# IR_Receiver.net
KiCad netlist of a schematic drawn in Altium Designer
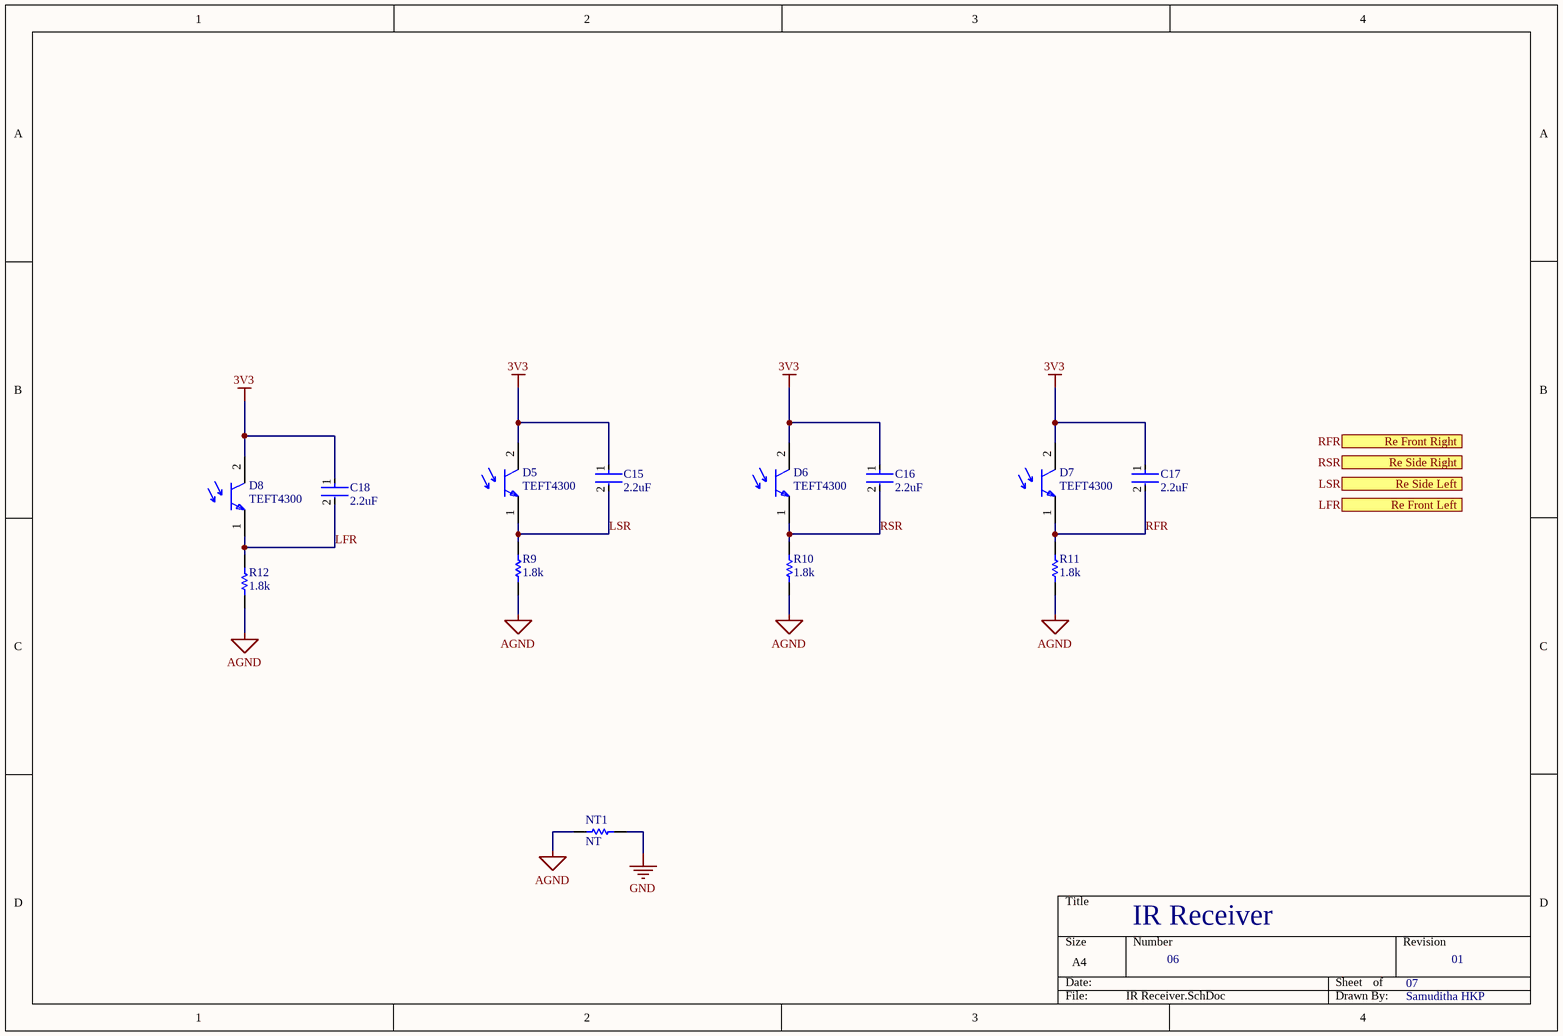
[diagram p0: IR Receiver.SchDoc]

(export (version "E")
  (design (tool "Eeschema 10.0.6"))
  (components
    (comp (ref "C15")
      (value "2.2uF")
      (footprint "FP-C0402C225M9PACTU-MFG")
      (description "CAP CER 2.2UF 6.3V X5R 0402")
      (fields (field (name "VOLTAGE") "6.3V") (field (name "TOLERANCE") "20%"))
      (libsource (lib "Altium Content Vault") (part "b4654b650e69147ec39a6b967a45e02"))
    )
    (comp (ref "C16")
      (value "2.2uF")
      (footprint "FP-C0402C225M9PACTU-MFG")
      (description "CAP CER 2.2UF 6.3V X5R 0402")
      (fields (field (name "VOLTAGE") "6.3V") (field (name "TOLERANCE") "20%"))
      (libsource (lib "Altium Content Vault") (part "b4654b650e69147ec39a6b967a45e02"))
    )
    (comp (ref "C17")
      (value "2.2uF")
      (footprint "FP-C0402C225M9PACTU-MFG")
      (description "CAP CER 2.2UF 6.3V X5R 0402")
      (fields (field (name "VOLTAGE") "6.3V") (field (name "TOLERANCE") "20%"))
      (libsource (lib "Altium Content Vault") (part "b4654b650e69147ec39a6b967a45e02"))
    )
    (comp (ref "C18")
      (value "2.2uF")
      (footprint "FP-C0402C225M9PACTU-MFG")
      (description "CAP CER 2.2UF 6.3V X5R 0402")
      (fields (field (name "VOLTAGE") "6.3V") (field (name "TOLERANCE") "20%"))
      (libsource (lib "Altium Content Vault") (part "b4654b650e69147ec39a6b967a45e02"))
    )
    (comp (ref "D5")
      (value "TEFT4300")
      (footprint "FP-6_544-5269_01-4-MFG")
      (description "TEFT4300 PHOTOTRANSISTOR 3.0MM WIDE VIEW / Phototransistor IR Chip Silicon 925nm 2-Pin T-1")
      (libsource (lib "Altium Content Vault") (part "fcf5d96e013ede1c9e051256f92411f"))
    )
    (comp (ref "D6")
      (value "TEFT4300")
      (footprint "FP-6_544-5269_01-4-MFG")
      (description "TEFT4300 PHOTOTRANSISTOR 3.0MM WIDE VIEW / Phototransistor IR Chip Silicon 925nm 2-Pin T-1")
      (libsource (lib "Altium Content Vault") (part "fcf5d96e013ede1c9e051256f92411f"))
    )
    (comp (ref "D7")
      (value "TEFT4300")
      (footprint "FP-6_544-5269_01-4-MFG")
      (description "TEFT4300 PHOTOTRANSISTOR 3.0MM WIDE VIEW / Phototransistor IR Chip Silicon 925nm 2-Pin T-1")
      (libsource (lib "Altium Content Vault") (part "fcf5d96e013ede1c9e051256f92411f"))
    )
    (comp (ref "D8")
      (value "TEFT4300")
      (footprint "FP-6_544-5269_01-4-MFG")
      (description "TEFT4300 PHOTOTRANSISTOR 3.0MM WIDE VIEW / Phototransistor IR Chip Silicon 925nm 2-Pin T-1")
      (libsource (lib "Altium Content Vault") (part "fcf5d96e013ede1c9e051256f92411f"))
    )
    (comp (ref "NT1")
      (value "NT")
      (footprint "RESC1005X40X25LL05T05")
      (fields (field (name "MANUFACTURER") "Panasonic") (field (name "PART NUMBER") "ERJ2RKF1801X"))
      (libsource (lib "Altium Content Vault") (part "RES"))
    )
    (comp (ref "R9")
      (value "1.8k")
      (footprint "RESC1005X40X25LL05T05")
      (fields (field (name "MANUFACTURER") "Panasonic") (field (name "PART NUMBER") "ERJ2RKF1801X"))
      (libsource (lib "Altium Content Vault") (part "RES"))
    )
    (comp (ref "R10")
      (value "1.8k")
      (footprint "RESC1005X40X25LL05T05")
      (fields (field (name "MANUFACTURER") "Panasonic") (field (name "PART NUMBER") "ERJ2RKF1801X"))
      (libsource (lib "Altium Content Vault") (part "RES"))
    )
    (comp (ref "R11")
      (value "1.8k")
      (footprint "RESC1005X40X25LL05T05")
      (fields (field (name "MANUFACTURER") "Panasonic") (field (name "PART NUMBER") "ERJ2RKF1801X"))
      (libsource (lib "Altium Content Vault") (part "RES"))
    )
    (comp (ref "R12")
      (value "1.8k")
      (footprint "RESC1005X40X25LL05T05")
      (fields (field (name "MANUFACTURER") "Panasonic") (field (name "PART NUMBER") "ERJ2RKF1801X"))
      (libsource (lib "Altium Content Vault") (part "RES"))
    )
  )
  (nets
    (net (code "1") (name "/LFR") (class "Default")
      (node (ref "C18") (pin "2") (pinfunction "2_2") (pintype "passive"))
      (node (ref "D8") (pin "1") (pinfunction "E_1") (pintype "passive"))
      (node (ref "R12") (pin "2") (pinfunction "2_2") (pintype "passive"))
    )
    (net (code "2") (name "/LSR") (class "Default")
      (node (ref "C15") (pin "2") (pinfunction "2_2") (pintype "passive"))
      (node (ref "D5") (pin "1") (pinfunction "E_1") (pintype "passive"))
      (node (ref "R9") (pin "2") (pinfunction "2_2") (pintype "passive"))
    )
    (net (code "3") (name "/RFR") (class "Default")
      (node (ref "C17") (pin "2") (pinfunction "2_2") (pintype "passive"))
      (node (ref "D7") (pin "1") (pinfunction "E_1") (pintype "passive"))
      (node (ref "R11") (pin "2") (pinfunction "2_2") (pintype "passive"))
    )
    (net (code "4") (name "/RSR") (class "Default")
      (node (ref "C16") (pin "2") (pinfunction "2_2") (pintype "passive"))
      (node (ref "D6") (pin "1") (pinfunction "E_1") (pintype "passive"))
      (node (ref "R10") (pin "2") (pinfunction "2_2") (pintype "passive"))
    )
    (net (code "9") (name "3V3") (class "Default")
      (node (ref "C15") (pin "1") (pinfunction "1_1") (pintype "passive"))
      (node (ref "C16") (pin "1") (pinfunction "1_1") (pintype "passive"))
      (node (ref "C17") (pin "1") (pinfunction "1_1") (pintype "passive"))
      (node (ref "C18") (pin "1") (pinfunction "1_1") (pintype "passive"))
      (node (ref "D5") (pin "2") (pinfunction "C_2") (pintype "passive"))
      (node (ref "D6") (pin "2") (pinfunction "C_2") (pintype "passive"))
      (node (ref "D7") (pin "2") (pinfunction "C_2") (pintype "passive"))
      (node (ref "D8") (pin "2") (pinfunction "C_2") (pintype "passive"))
    )
    (net (code "10") (name "AGND") (class "Default")
      (node (ref "NT1") (pin "2") (pinfunction "2_2") (pintype "passive"))
      (node (ref "R10") (pin "1") (pinfunction "1_1") (pintype "passive"))
      (node (ref "R11") (pin "1") (pinfunction "1_1") (pintype "passive"))
      (node (ref "R12") (pin "1") (pinfunction "1_1") (pintype "passive"))
      (node (ref "R9") (pin "1") (pinfunction "1_1") (pintype "passive"))
    )
    (net (code "11") (name "GND") (class "Default")
      (node (ref "NT1") (pin "1") (pinfunction "1_1") (pintype "passive"))
    )
  )
)
